# Zio_Line_Finder.net
KiCad netlist of a schematic drawn in EAGLE
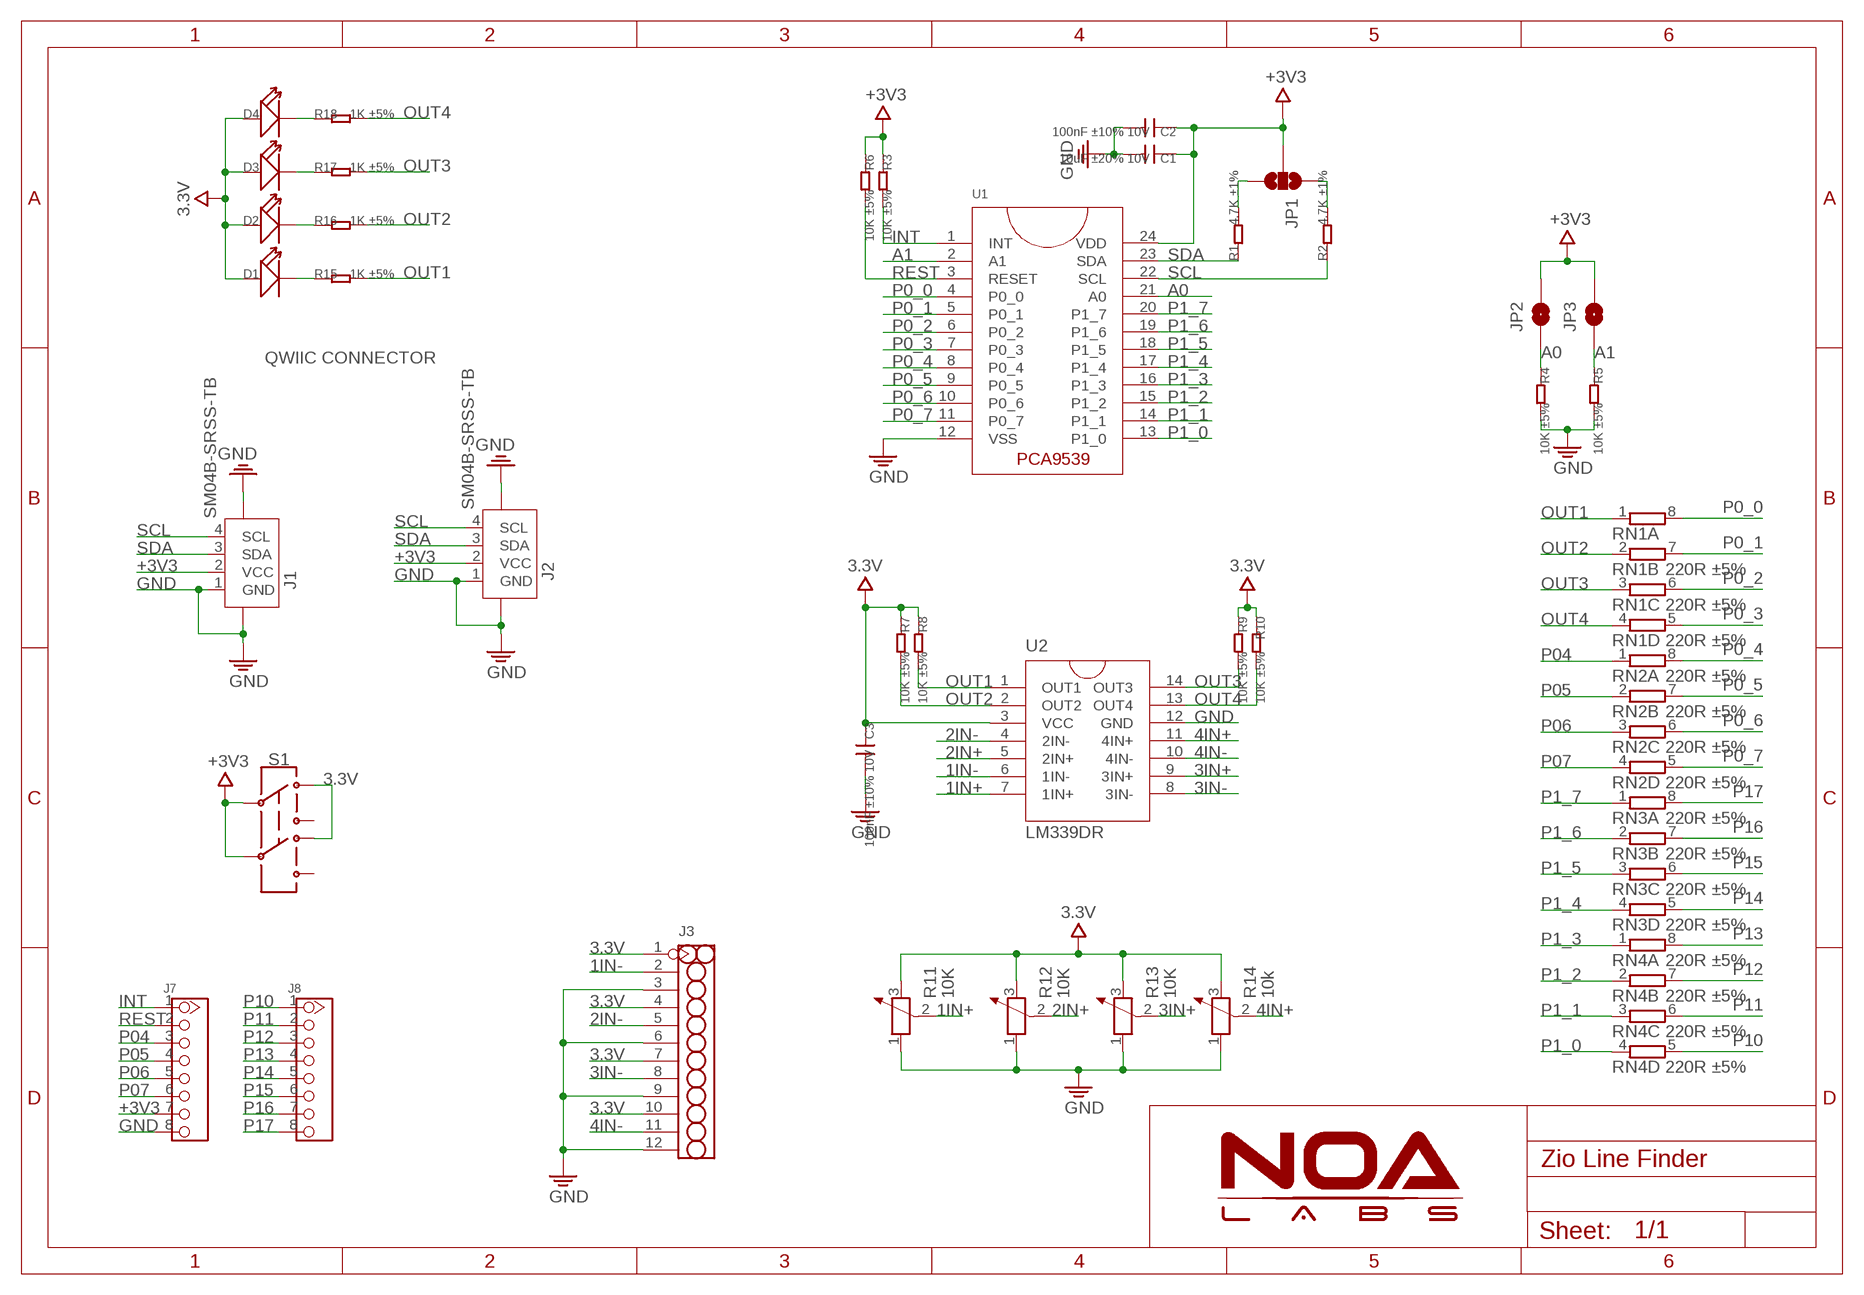
[diagram p0: schematic, sheet 1]

(export (version "E")
  (design (tool "Eeschema 10.0.6"))
  (components
    (comp (ref "C1")
      (value "10uF ±20% 10V")
      (footprint "eagle-import:0603")
      (libsource (lib "eagle-import") (part "C-0603"))
    )
    (comp (ref "C2")
      (value "100nF ±10% 10V")
      (footprint "eagle-import:0603")
      (libsource (lib "eagle-import") (part "C-0603"))
    )
    (comp (ref "C3")
      (value "100nF ±10% 10V")
      (footprint "eagle-import:0603")
      (libsource (lib "eagle-import") (part "C-0603"))
    )
    (comp (ref "D1")
      (value "LED'0603'")
      (footprint "eagle-import:LED-0603")
      (libsource (lib "eagle-import") (part "LED'0603'"))
    )
    (comp (ref "D2")
      (value "LED'0603'")
      (footprint "eagle-import:LED-0603")
      (libsource (lib "eagle-import") (part "LED'0603'"))
    )
    (comp (ref "D3")
      (value "LED'0603'")
      (footprint "eagle-import:LED-0603")
      (libsource (lib "eagle-import") (part "LED'0603'"))
    )
    (comp (ref "D4")
      (value "LED'0603'")
      (footprint "eagle-import:LED-0603")
      (libsource (lib "eagle-import") (part "LED'0603'"))
    )
    (comp (ref "J1")
      (value "SM04B-SRSS-TB")
      (footprint "eagle-import:JST-SH-4P")
      (libsource (lib "eagle-import") (part "JST-SH-4P-1.0"))
    )
    (comp (ref "J2")
      (value "SM04B-SRSS-TB")
      (footprint "eagle-import:JST-SH-4P")
      (libsource (lib "eagle-import") (part "JST-SH-4P-1.0"))
    )
    (comp (ref "J3")
      (value "HEADER-12P-2.54")
      (footprint "eagle-import:12P-2.54")
      (libsource (lib "eagle-import") (part "HEADER-12P-2.54"))
    )
    (comp (ref "J7")
      (value "HEADER-8P-60/35MIL")
      (footprint "eagle-import:8P-2.54-60_35MIL")
      (libsource (lib "eagle-import") (part "HEADER-8P-60/35MIL"))
    )
    (comp (ref "J8")
      (value "HEADER-8P-60/35MIL")
      (footprint "eagle-import:8P-2.54-60_35MIL")
      (libsource (lib "eagle-import") (part "HEADER-8P-60/35MIL"))
    )
    (comp (ref "JP1")
      (value "JUMPER-SMT_3_2-NC_PASTE_NOCREM")
      (footprint "eagle-import:SMT-JUMPER_3_2-NC_PASTE_SILK_NOCREM")
      (libsource (lib "eagle-import") (part "JUMPER-SMT_3_2-NC_PASTE_NOCREM"))
    )
    (comp (ref "JP2")
      (value "JUMPER-SMT_2_NC_PASTE_NOCREM")
      (footprint "eagle-import:SMT-JUMPER_2_NC_PASTE_SILK_NOCREM")
      (libsource (lib "eagle-import") (part "JUMPER-SMT_2_NC_PASTE_NOCREM"))
    )
    (comp (ref "JP3")
      (value "JUMPER-SMT_2_NC_PASTE_NOCREM")
      (footprint "eagle-import:SMT-JUMPER_2_NC_PASTE_SILK_NOCREM")
      (libsource (lib "eagle-import") (part "JUMPER-SMT_2_NC_PASTE_NOCREM"))
    )
    (comp (ref "R1")
      (value "4.7K ±1%")
      (footprint "eagle-import:0402")
      (libsource (lib "eagle-import") (part "Discretex_R-0402"))
    )
    (comp (ref "R2")
      (value "4.7K ±1%")
      (footprint "eagle-import:0402")
      (libsource (lib "eagle-import") (part "Discretex_R-0402"))
    )
    (comp (ref "R3")
      (value "10K ±5%")
      (footprint "eagle-import:0402")
      (libsource (lib "eagle-import") (part "R-0402"))
    )
    (comp (ref "R4")
      (value "10K ±5%")
      (footprint "eagle-import:0402")
      (libsource (lib "eagle-import") (part "R-0402"))
    )
    (comp (ref "R5")
      (value "10K ±5%")
      (footprint "eagle-import:0402")
      (libsource (lib "eagle-import") (part "R-0402"))
    )
    (comp (ref "R6")
      (value "10K ±5%")
      (footprint "eagle-import:0402")
      (libsource (lib "eagle-import") (part "R-0402"))
    )
    (comp (ref "R7")
      (value "10K ±5%")
      (footprint "eagle-import:0402")
      (libsource (lib "eagle-import") (part "R-0402"))
    )
    (comp (ref "R8")
      (value "10K ±5%")
      (footprint "eagle-import:0402")
      (libsource (lib "eagle-import") (part "R-0402"))
    )
    (comp (ref "R9")
      (value "10K ±5%")
      (footprint "eagle-import:0402")
      (libsource (lib "eagle-import") (part "R-0402"))
    )
    (comp (ref "R10")
      (value "10K ±5%")
      (footprint "eagle-import:0402")
      (libsource (lib "eagle-import") (part "R-0402"))
    )
    (comp (ref "R11")
      (value "10K")
      (footprint "eagle-import:3P-SQUA-7X6.8")
      (libsource (lib "eagle-import") (part "R-POTENTIOMETER'3362'"))
    )
    (comp (ref "R12")
      (value "10K")
      (footprint "eagle-import:3P-SQUA-7X6.8")
      (libsource (lib "eagle-import") (part "R-POTENTIOMETER'3362'"))
    )
    (comp (ref "R13")
      (value "10K")
      (footprint "eagle-import:3P-SQUA-7X6.8")
      (libsource (lib "eagle-import") (part "R-POTENTIOMETER'3362'"))
    )
    (comp (ref "R14")
      (value "10k")
      (footprint "eagle-import:3P-SQUA-7X6.8")
      (libsource (lib "eagle-import") (part "R-POTENTIOMETER'3362'"))
    )
    (comp (ref "R15")
      (value "1K ±5%")
      (footprint "eagle-import:0402")
      (libsource (lib "eagle-import") (part "R-0402"))
    )
    (comp (ref "R16")
      (value "1K ±5%")
      (footprint "eagle-import:0402")
      (libsource (lib "eagle-import") (part "R-0402"))
    )
    (comp (ref "R17")
      (value "1K ±5%")
      (footprint "eagle-import:0402")
      (libsource (lib "eagle-import") (part "R-0402"))
    )
    (comp (ref "R18")
      (value "1K ±5%")
      (footprint "eagle-import:0402")
      (libsource (lib "eagle-import") (part "R-0402"))
    )
    (comp (ref "RN1")
      (value "220R ±5%")
      (footprint "eagle-import:RESISTOR-DIL_0603-ARV")
      (libsource (lib "eagle-import") (part "RESISTOR-DIL_4R-N0603-ARV"))
    )
    (comp (ref "RN2")
      (value "220R ±5%")
      (footprint "eagle-import:RESISTOR-DIL_0603-ARV")
      (libsource (lib "eagle-import") (part "RESISTOR-DIL_4R-N0603-ARV"))
    )
    (comp (ref "RN3")
      (value "220R ±5%")
      (footprint "eagle-import:RESISTOR-DIL_0603-ARV")
      (libsource (lib "eagle-import") (part "RESISTOR-DIL_4R-N0603-ARV"))
    )
    (comp (ref "RN4")
      (value "220R ±5%")
      (footprint "eagle-import:RESISTOR-DIL_0603-ARV")
      (libsource (lib "eagle-import") (part "RESISTOR-DIL_4R-N0603-ARV"))
    )
    (comp (ref "S1")
      (value "SWITCH-DPDT-SMD-AYZ0202")
      (footprint "eagle-import:SWITCH_DPDT_SMD_AYZ0202")
      (libsource (lib "eagle-import") (part "SWITCH-DPDT-SMD-AYZ0202"))
    )
    (comp (ref "U1")
      (value "PCA9539")
      (footprint "eagle-import:TSSOP24")
      (libsource (lib "eagle-import") (part "PCA9539"))
    )
    (comp (ref "U2")
      (value "LM339DR")
      (footprint "eagle-import:SOIC14-8.7")
      (libsource (lib "eagle-import") (part "LM339"))
    )
  )
  (nets
    (net (code "1") (name "+3V3") (class "Default")
      (node (ref "C1") (pin "1") (pinfunction "1_1") (pintype "passive"))
      (node (ref "C2") (pin "1") (pinfunction "1_1") (pintype "passive"))
      (node (ref "J1") (pin "2") (pinfunction "VCC_2") (pintype "bidirectional"))
      (node (ref "J2") (pin "2") (pinfunction "VCC_2") (pintype "bidirectional"))
      (node (ref "J7") (pin "7") (pinfunction "7_7") (pintype "bidirectional"))
      (node (ref "JP1") (pin "2") (pinfunction "2_2") (pintype "passive"))
      (node (ref "JP2") (pin "2") (pinfunction "2_2") (pintype "passive"))
      (node (ref "JP3") (pin "2") (pinfunction "2_2") (pintype "passive"))
      (node (ref "R3") (pin "1") (pinfunction "1_1") (pintype "passive"))
      (node (ref "R6") (pin "1") (pinfunction "1_1") (pintype "passive"))
      (node (ref "S1") (pin "2") (pinfunction "2_2") (pintype "bidirectional"))
      (node (ref "S1") (pin "5") (pinfunction "5_5") (pintype "bidirectional"))
      (node (ref "U1") (pin "24") (pinfunction "VDD_24") (pintype "bidirectional"))
    )
    (net (code "2") (name "/1IN+") (class "Default")
      (node (ref "R11") (pin "2") (pinfunction "2_2") (pintype "passive"))
      (node (ref "U2") (pin "7") (pinfunction "1IN+_7") (pintype "bidirectional"))
    )
    (net (code "3") (name "/1IN-") (class "Default")
      (node (ref "J3") (pin "2") (pinfunction "2_2") (pintype "bidirectional"))
      (node (ref "U2") (pin "6") (pinfunction "1IN-_6") (pintype "bidirectional"))
    )
    (net (code "4") (name "/2IN+") (class "Default")
      (node (ref "R12") (pin "2") (pinfunction "2_2") (pintype "passive"))
      (node (ref "U2") (pin "5") (pinfunction "2IN+_5") (pintype "bidirectional"))
    )
    (net (code "5") (name "/2IN-") (class "Default")
      (node (ref "J3") (pin "5") (pinfunction "5_5") (pintype "bidirectional"))
      (node (ref "U2") (pin "4") (pinfunction "2IN-_4") (pintype "bidirectional"))
    )
    (net (code "6") (name "/3IN+") (class "Default")
      (node (ref "R13") (pin "2") (pinfunction "2_2") (pintype "passive"))
      (node (ref "U2") (pin "9") (pinfunction "3IN+_9") (pintype "bidirectional"))
    )
    (net (code "7") (name "/3IN-") (class "Default")
      (node (ref "J3") (pin "8") (pinfunction "8_8") (pintype "bidirectional"))
      (node (ref "U2") (pin "8") (pinfunction "3IN-_8") (pintype "bidirectional"))
    )
    (net (code "8") (name "/4IN+") (class "Default")
      (node (ref "R14") (pin "2") (pinfunction "2_2") (pintype "passive"))
      (node (ref "U2") (pin "11") (pinfunction "4IN+_11") (pintype "bidirectional"))
    )
    (net (code "9") (name "/4IN-") (class "Default")
      (node (ref "J3") (pin "11") (pinfunction "11_11") (pintype "bidirectional"))
      (node (ref "U2") (pin "10") (pinfunction "4IN-_10") (pintype "bidirectional"))
    )
    (net (code "10") (name "/A0") (class "Default")
      (node (ref "JP2") (pin "1") (pinfunction "1_1") (pintype "passive"))
      (node (ref "R4") (pin "1") (pinfunction "1_1") (pintype "passive"))
      (node (ref "U1") (pin "21") (pinfunction "A0_21") (pintype "bidirectional"))
    )
    (net (code "11") (name "/A1") (class "Default")
      (node (ref "JP3") (pin "1") (pinfunction "1_1") (pintype "passive"))
      (node (ref "R5") (pin "1") (pinfunction "1_1") (pintype "passive"))
      (node (ref "U1") (pin "2") (pinfunction "A1_2") (pintype "bidirectional"))
    )
    (net (code "12") (name "/INT") (class "Default")
      (node (ref "J7") (pin "1") (pinfunction "1_1") (pintype "bidirectional"))
      (node (ref "R3") (pin "2") (pinfunction "2_2") (pintype "passive"))
      (node (ref "U1") (pin "1") (pinfunction "INT_1") (pintype "bidirectional"))
    )
    (net (code "13") (name "/OUT1") (class "Default")
      (node (ref "R15") (pin "2") (pinfunction "2_2") (pintype "passive"))
      (node (ref "R8") (pin "2") (pinfunction "2_2") (pintype "passive"))
      (node (ref "RN1") (pin "1") (pinfunction "1_1") (pintype "passive"))
      (node (ref "U2") (pin "1") (pinfunction "OUT1_1") (pintype "bidirectional"))
    )
    (net (code "14") (name "/OUT2") (class "Default")
      (node (ref "R16") (pin "2") (pinfunction "2_2") (pintype "passive"))
      (node (ref "R7") (pin "2") (pinfunction "2_2") (pintype "passive"))
      (node (ref "RN1") (pin "2") (pinfunction "1_2") (pintype "passive"))
      (node (ref "U2") (pin "2") (pinfunction "OUT2_2") (pintype "bidirectional"))
    )
    (net (code "15") (name "/OUT3") (class "Default")
      (node (ref "R17") (pin "2") (pinfunction "2_2") (pintype "passive"))
      (node (ref "R9") (pin "2") (pinfunction "2_2") (pintype "passive"))
      (node (ref "RN1") (pin "3") (pinfunction "1_3") (pintype "passive"))
      (node (ref "U2") (pin "14") (pinfunction "OUT3_14") (pintype "bidirectional"))
    )
    (net (code "16") (name "/OUT4") (class "Default")
      (node (ref "R10") (pin "2") (pinfunction "2_2") (pintype "passive"))
      (node (ref "R18") (pin "2") (pinfunction "2_2") (pintype "passive"))
      (node (ref "RN1") (pin "4") (pinfunction "1_4") (pintype "passive"))
      (node (ref "U2") (pin "13") (pinfunction "OUT4_13") (pintype "bidirectional"))
    )
    (net (code "17") (name "/P0_0") (class "Default")
      (node (ref "RN1") (pin "8") (pinfunction "2_8") (pintype "passive"))
      (node (ref "U1") (pin "4") (pinfunction "P0_0_4") (pintype "bidirectional"))
    )
    (net (code "18") (name "/P0_1") (class "Default")
      (node (ref "RN1") (pin "7") (pinfunction "2_7") (pintype "passive"))
      (node (ref "U1") (pin "5") (pinfunction "P0_1_5") (pintype "bidirectional"))
    )
    (net (code "19") (name "/P0_2") (class "Default")
      (node (ref "RN1") (pin "6") (pinfunction "2_6") (pintype "passive"))
      (node (ref "U1") (pin "6") (pinfunction "P0_2_6") (pintype "bidirectional"))
    )
    (net (code "20") (name "/P0_3") (class "Default")
      (node (ref "RN1") (pin "5") (pinfunction "2_5") (pintype "passive"))
      (node (ref "U1") (pin "7") (pinfunction "P0_3_7") (pintype "bidirectional"))
    )
    (net (code "21") (name "/P0_4") (class "Default")
      (node (ref "RN2") (pin "8") (pinfunction "2_8") (pintype "passive"))
      (node (ref "U1") (pin "8") (pinfunction "P0_4_8") (pintype "bidirectional"))
    )
    (net (code "22") (name "/P0_5") (class "Default")
      (node (ref "RN2") (pin "7") (pinfunction "2_7") (pintype "passive"))
      (node (ref "U1") (pin "9") (pinfunction "P0_5_9") (pintype "bidirectional"))
    )
    (net (code "23") (name "/P0_6") (class "Default")
      (node (ref "RN2") (pin "6") (pinfunction "2_6") (pintype "passive"))
      (node (ref "U1") (pin "10") (pinfunction "P0_6_10") (pintype "bidirectional"))
    )
    (net (code "24") (name "/P0_7") (class "Default")
      (node (ref "RN2") (pin "5") (pinfunction "2_5") (pintype "passive"))
      (node (ref "U1") (pin "11") (pinfunction "P0_7_11") (pintype "bidirectional"))
    )
    (net (code "25") (name "/P1_0") (class "Default")
      (node (ref "RN4") (pin "4") (pinfunction "1_4") (pintype "passive"))
      (node (ref "U1") (pin "13") (pinfunction "P1_0_13") (pintype "bidirectional"))
    )
    (net (code "26") (name "/P1_1") (class "Default")
      (node (ref "RN4") (pin "3") (pinfunction "1_3") (pintype "passive"))
      (node (ref "U1") (pin "14") (pinfunction "P1_1_14") (pintype "bidirectional"))
    )
    (net (code "27") (name "/P1_2") (class "Default")
      (node (ref "RN4") (pin "2") (pinfunction "1_2") (pintype "passive"))
      (node (ref "U1") (pin "15") (pinfunction "P1_2_15") (pintype "bidirectional"))
    )
    (net (code "28") (name "/P1_3") (class "Default")
      (node (ref "RN4") (pin "1") (pinfunction "1_1") (pintype "passive"))
      (node (ref "U1") (pin "16") (pinfunction "P1_3_16") (pintype "bidirectional"))
    )
    (net (code "29") (name "/P1_4") (class "Default")
      (node (ref "RN3") (pin "4") (pinfunction "1_4") (pintype "passive"))
      (node (ref "U1") (pin "17") (pinfunction "P1_4_17") (pintype "bidirectional"))
    )
    (net (code "30") (name "/P1_5") (class "Default")
      (node (ref "RN3") (pin "3") (pinfunction "1_3") (pintype "passive"))
      (node (ref "U1") (pin "18") (pinfunction "P1_5_18") (pintype "bidirectional"))
    )
    (net (code "31") (name "/P1_6") (class "Default")
      (node (ref "RN3") (pin "2") (pinfunction "1_2") (pintype "passive"))
      (node (ref "U1") (pin "19") (pinfunction "P1_6_19") (pintype "bidirectional"))
    )
    (net (code "32") (name "/P1_7") (class "Default")
      (node (ref "RN3") (pin "1") (pinfunction "1_1") (pintype "passive"))
      (node (ref "U1") (pin "20") (pinfunction "P1_7_20") (pintype "bidirectional"))
    )
    (net (code "33") (name "/P04") (class "Default")
      (node (ref "J7") (pin "3") (pinfunction "3_3") (pintype "bidirectional"))
      (node (ref "RN2") (pin "1") (pinfunction "1_1") (pintype "passive"))
    )
    (net (code "34") (name "/P05") (class "Default")
      (node (ref "J7") (pin "4") (pinfunction "4_4") (pintype "bidirectional"))
      (node (ref "RN2") (pin "2") (pinfunction "1_2") (pintype "passive"))
    )
    (net (code "35") (name "/P06") (class "Default")
      (node (ref "J7") (pin "5") (pinfunction "5_5") (pintype "bidirectional"))
      (node (ref "RN2") (pin "3") (pinfunction "1_3") (pintype "passive"))
    )
    (net (code "36") (name "/P07") (class "Default")
      (node (ref "J7") (pin "6") (pinfunction "6_6") (pintype "bidirectional"))
      (node (ref "RN2") (pin "4") (pinfunction "1_4") (pintype "passive"))
    )
    (net (code "37") (name "/P10") (class "Default")
      (node (ref "J8") (pin "1") (pinfunction "1_1") (pintype "bidirectional"))
      (node (ref "RN4") (pin "5") (pinfunction "2_5") (pintype "passive"))
    )
    (net (code "38") (name "/P11") (class "Default")
      (node (ref "J8") (pin "2") (pinfunction "2_2") (pintype "bidirectional"))
      (node (ref "RN4") (pin "6") (pinfunction "2_6") (pintype "passive"))
    )
    (net (code "39") (name "/P12") (class "Default")
      (node (ref "J8") (pin "3") (pinfunction "3_3") (pintype "bidirectional"))
      (node (ref "RN4") (pin "7") (pinfunction "2_7") (pintype "passive"))
    )
    (net (code "40") (name "/P13") (class "Default")
      (node (ref "J8") (pin "4") (pinfunction "4_4") (pintype "bidirectional"))
      (node (ref "RN4") (pin "8") (pinfunction "2_8") (pintype "passive"))
    )
    (net (code "41") (name "/P14") (class "Default")
      (node (ref "J8") (pin "5") (pinfunction "5_5") (pintype "bidirectional"))
      (node (ref "RN3") (pin "5") (pinfunction "2_5") (pintype "passive"))
    )
    (net (code "42") (name "/P15") (class "Default")
      (node (ref "J8") (pin "6") (pinfunction "6_6") (pintype "bidirectional"))
      (node (ref "RN3") (pin "6") (pinfunction "2_6") (pintype "passive"))
    )
    (net (code "43") (name "/P16") (class "Default")
      (node (ref "J8") (pin "7") (pinfunction "7_7") (pintype "bidirectional"))
      (node (ref "RN3") (pin "7") (pinfunction "2_7") (pintype "passive"))
    )
    (net (code "44") (name "/P17") (class "Default")
      (node (ref "J8") (pin "8") (pinfunction "8_8") (pintype "bidirectional"))
      (node (ref "RN3") (pin "8") (pinfunction "2_8") (pintype "passive"))
    )
    (net (code "45") (name "/REST") (class "Default")
      (node (ref "J7") (pin "2") (pinfunction "2_2") (pintype "bidirectional"))
      (node (ref "R6") (pin "2") (pinfunction "2_2") (pintype "passive"))
      (node (ref "U1") (pin "3") (pinfunction "RESET_3") (pintype "bidirectional"))
    )
    (net (code "46") (name "/SCL") (class "Default")
      (node (ref "J1") (pin "4") (pinfunction "SCL_4") (pintype "bidirectional"))
      (node (ref "J2") (pin "4") (pinfunction "SCL_4") (pintype "bidirectional"))
      (node (ref "R2") (pin "1") (pinfunction "1_1") (pintype "passive"))
      (node (ref "U1") (pin "22") (pinfunction "SCL_22") (pintype "bidirectional"))
    )
    (net (code "47") (name "/SDA") (class "Default")
      (node (ref "J1") (pin "3") (pinfunction "SDA_3") (pintype "bidirectional"))
      (node (ref "J2") (pin "3") (pinfunction "SDA_3") (pintype "bidirectional"))
      (node (ref "R1") (pin "1") (pinfunction "1_1") (pintype "passive"))
      (node (ref "U1") (pin "23") (pinfunction "SDA_23") (pintype "bidirectional"))
    )
    (net (code "48") (name "3.3V") (class "Default")
      (node (ref "C3") (pin "1") (pinfunction "1_1") (pintype "passive"))
      (node (ref "D1") (pin "+") (pinfunction "+_+") (pintype "passive"))
      (node (ref "D2") (pin "+") (pinfunction "+_+") (pintype "passive"))
      (node (ref "D3") (pin "+") (pinfunction "+_+") (pintype "passive"))
      (node (ref "D4") (pin "+") (pinfunction "+_+") (pintype "passive"))
      (node (ref "J3") (pin "1") (pinfunction "1_1") (pintype "bidirectional"))
      (node (ref "J3") (pin "10") (pinfunction "10_10") (pintype "bidirectional"))
      (node (ref "J3") (pin "4") (pinfunction "4_4") (pintype "bidirectional"))
      (node (ref "J3") (pin "7") (pinfunction "7_7") (pintype "bidirectional"))
      (node (ref "R10") (pin "1") (pinfunction "1_1") (pintype "passive"))
      (node (ref "R11") (pin "3") (pinfunction "3_3") (pintype "passive"))
      (node (ref "R12") (pin "3") (pinfunction "3_3") (pintype "passive"))
      (node (ref "R13") (pin "3") (pinfunction "3_3") (pintype "passive"))
      (node (ref "R14") (pin "3") (pinfunction "3_3") (pintype "passive"))
      (node (ref "R7") (pin "1") (pinfunction "1_1") (pintype "passive"))
      (node (ref "R8") (pin "1") (pinfunction "1_1") (pintype "passive"))
      (node (ref "R9") (pin "1") (pinfunction "1_1") (pintype "passive"))
      (node (ref "S1") (pin "1") (pinfunction "1_1") (pintype "bidirectional"))
      (node (ref "S1") (pin "4") (pinfunction "4_4") (pintype "bidirectional"))
      (node (ref "U2") (pin "3") (pinfunction "VCC_3") (pintype "bidirectional"))
    )
    (net (code "49") (name "GND") (class "Default")
      (node (ref "C1") (pin "2") (pinfunction "2_2") (pintype "passive"))
      (node (ref "C2") (pin "2") (pinfunction "2_2") (pintype "passive"))
      (node (ref "C3") (pin "2") (pinfunction "2_2") (pintype "passive"))
      (node (ref "J1") (pin "1") (pinfunction "GND_1") (pintype "bidirectional"))
      (node (ref "J1") (pin "NC1") (pinfunction "5_NC1") (pintype "bidirectional"))
      (node (ref "J1") (pin "NC2") (pinfunction "6_NC2") (pintype "bidirectional"))
      (node (ref "J2") (pin "1") (pinfunction "GND_1") (pintype "bidirectional"))
      (node (ref "J2") (pin "NC1") (pinfunction "5_NC1") (pintype "bidirectional"))
      (node (ref "J2") (pin "NC2") (pinfunction "6_NC2") (pintype "bidirectional"))
      (node (ref "J3") (pin "12") (pinfunction "12_12") (pintype "bidirectional"))
      (node (ref "J3") (pin "3") (pinfunction "3_3") (pintype "bidirectional"))
      (node (ref "J3") (pin "6") (pinfunction "6_6") (pintype "bidirectional"))
      (node (ref "J3") (pin "9") (pinfunction "9_9") (pintype "bidirectional"))
      (node (ref "J7") (pin "8") (pinfunction "8_8") (pintype "bidirectional"))
      (node (ref "R11") (pin "1") (pinfunction "1_1") (pintype "passive"))
      (node (ref "R12") (pin "1") (pinfunction "1_1") (pintype "passive"))
      (node (ref "R13") (pin "1") (pinfunction "1_1") (pintype "passive"))
      (node (ref "R14") (pin "1") (pinfunction "1_1") (pintype "passive"))
      (node (ref "R4") (pin "2") (pinfunction "2_2") (pintype "passive"))
      (node (ref "R5") (pin "2") (pinfunction "2_2") (pintype "passive"))
      (node (ref "U1") (pin "12") (pinfunction "VSS_12") (pintype "bidirectional"))
      (node (ref "U2") (pin "12") (pinfunction "GND_12") (pintype "bidirectional"))
    )
    (net (code "50") (name "Net-(D1-Pad-)") (class "Default")
      (node (ref "D1") (pin "-") (pinfunction "-_-") (pintype "passive"))
      (node (ref "R15") (pin "1") (pinfunction "1_1") (pintype "passive"))
    )
    (net (code "51") (name "Net-(D2-Pad-)") (class "Default")
      (node (ref "D2") (pin "-") (pinfunction "-_-") (pintype "passive"))
      (node (ref "R16") (pin "1") (pinfunction "1_1") (pintype "passive"))
    )
    (net (code "52") (name "Net-(D3-Pad-)") (class "Default")
      (node (ref "D3") (pin "-") (pinfunction "-_-") (pintype "passive"))
      (node (ref "R17") (pin "1") (pinfunction "1_1") (pintype "passive"))
    )
    (net (code "53") (name "Net-(D4-Pad-)") (class "Default")
      (node (ref "D4") (pin "-") (pinfunction "-_-") (pintype "passive"))
      (node (ref "R18") (pin "1") (pinfunction "1_1") (pintype "passive"))
    )
    (net (code "54") (name "Net-(JP1-Pad1)") (class "Default")
      (node (ref "JP1") (pin "1") (pinfunction "1_1") (pintype "passive"))
      (node (ref "R2") (pin "2") (pinfunction "2_2") (pintype "passive"))
    )
    (net (code "55") (name "Net-(JP1-Pad3)") (class "Default")
      (node (ref "JP1") (pin "3") (pinfunction "3_3") (pintype "passive"))
      (node (ref "R1") (pin "2") (pinfunction "2_2") (pintype "passive"))
    )
    (net (code "56") (name "unconnected-(S1-Pad3)") (class "Default")
      (node (ref "S1") (pin "3") (pinfunction "3_3") (pintype "bidirectional"))
    )
    (net (code "57") (name "unconnected-(S1-Pad6)") (class "Default")
      (node (ref "S1") (pin "6") (pinfunction "6_6") (pintype "bidirectional"))
    )
  )
)
